# massmfg_tinyx4_v1_2.net
KiCad netlist of a schematic drawn in EAGLE
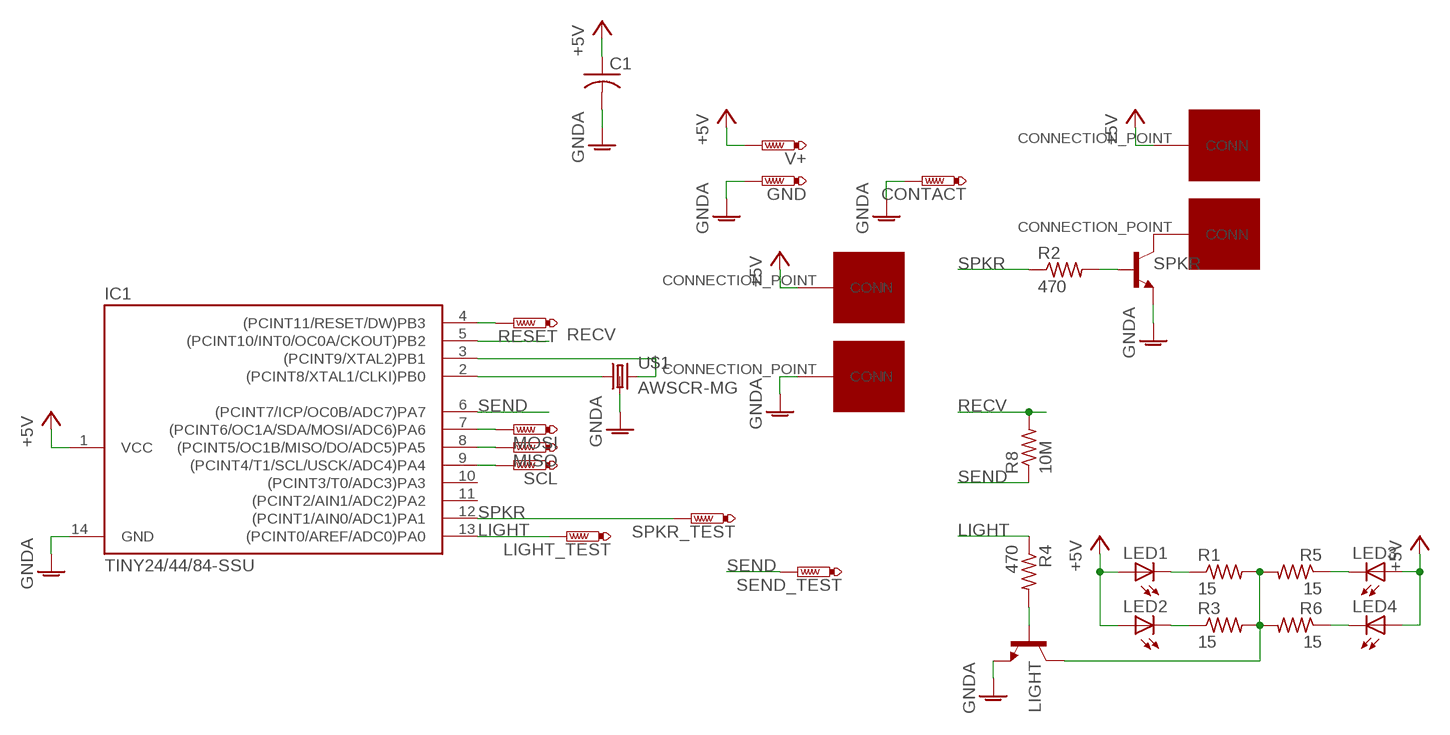
[diagram p0: schematic, sheet 1]

(export (version "E")
  (design (tool "Eeschema 10.0.6"))
  (components
    (comp (ref "C1")
      (value "C-USC0603")
      (footprint "eagle-import:C0603")
      (libsource (lib "eagle-import") (part "C-USC0603"))
    )
    (comp (ref "CONTACT")
      (value "PTR1")
      (footprint "eagle-import:P1-06")
      (libsource (lib "eagle-import") (part "PTR1"))
    )
    (comp (ref "GND")
      (value "PTR1")
      (footprint "eagle-import:P1-06")
      (libsource (lib "eagle-import") (part "PTR1"))
    )
    (comp (ref "IC1")
      (value "TINY24/44/84-SSU")
      (footprint "eagle-import:SOIC14")
      (libsource (lib "eagle-import") (part "TINY24/44/84-SSU"))
    )
    (comp (ref "LED1")
      (value "LEDOPTEK-DURIS5")
      (footprint "eagle-import:OPTEK-DURIS5")
      (libsource (lib "eagle-import") (part "LEDOPTEK-DURIS5"))
    )
    (comp (ref "LED2")
      (value "LEDOPTEK-DURIS5")
      (footprint "eagle-import:OPTEK-DURIS5")
      (libsource (lib "eagle-import") (part "LEDOPTEK-DURIS5"))
    )
    (comp (ref "LED3")
      (value "LEDOPTEK-DURIS5")
      (footprint "eagle-import:OPTEK-DURIS5")
      (libsource (lib "eagle-import") (part "LEDOPTEK-DURIS5"))
    )
    (comp (ref "LED4")
      (value "LEDOPTEK-DURIS5")
      (footprint "eagle-import:OPTEK-DURIS5")
      (libsource (lib "eagle-import") (part "LEDOPTEK-DURIS5"))
    )
    (comp (ref "LIGHT")
      (value "SOT23-BEC")
      (footprint "eagle-import:SOT23-BEC")
      (libsource (lib "eagle-import") (part "SOT23-BEC"))
    )
    (comp (ref "LIGHT_TEST")
      (value "PTR1")
      (footprint "eagle-import:P1-06")
      (libsource (lib "eagle-import") (part "PTR1"))
    )
    (comp (ref "MISO")
      (value "PTR1")
      (footprint "eagle-import:P1-06")
      (libsource (lib "eagle-import") (part "PTR1"))
    )
    (comp (ref "MOSI")
      (value "PTR1")
      (footprint "eagle-import:P1-06")
      (libsource (lib "eagle-import") (part "PTR1"))
    )
    (comp (ref "R1")
      (value "15")
      (footprint "eagle-import:M1206")
      (libsource (lib "eagle-import") (part "R-US_M1206"))
    )
    (comp (ref "R2")
      (value "470")
      (footprint "eagle-import:R0805")
      (libsource (lib "eagle-import") (part "R-US_R0805"))
    )
    (comp (ref "R3")
      (value "15")
      (footprint "eagle-import:M1206")
      (libsource (lib "eagle-import") (part "R-US_M1206"))
    )
    (comp (ref "R4")
      (value "470")
      (footprint "eagle-import:R0805")
      (libsource (lib "eagle-import") (part "R-US_R0805"))
    )
    (comp (ref "R5")
      (value "15")
      (footprint "eagle-import:M1206")
      (libsource (lib "eagle-import") (part "R-US_M1206"))
    )
    (comp (ref "R6")
      (value "15")
      (footprint "eagle-import:M1206")
      (libsource (lib "eagle-import") (part "R-US_M1206"))
    )
    (comp (ref "R8")
      (value "10M")
      (footprint "eagle-import:M1206")
      (libsource (lib "eagle-import") (part "R-US_M1206"))
    )
    (comp (ref "RESET")
      (value "PTR1")
      (footprint "eagle-import:P1-06")
      (libsource (lib "eagle-import") (part "PTR1"))
    )
    (comp (ref "SCL")
      (value "PTR1")
      (footprint "eagle-import:P1-06")
      (libsource (lib "eagle-import") (part "PTR1"))
    )
    (comp (ref "SEND_TEST")
      (value "PTR1")
      (footprint "eagle-import:P1-06")
      (libsource (lib "eagle-import") (part "PTR1"))
    )
    (comp (ref "SPEAKER_PLUS")
      (value "CONNECTION_POINT")
      (footprint "eagle-import:10X3_CONNECTION_POINT")
      (libsource (lib "eagle-import") (part "CONNECTION_POINT"))
    )
    (comp (ref "SPKR")
      (value "SOT23-BEC")
      (footprint "eagle-import:SOT23-BEC")
      (libsource (lib "eagle-import") (part "SOT23-BEC"))
    )
    (comp (ref "SPKR_MINUS")
      (value "CONNECTION_POINT")
      (footprint "eagle-import:10X3_CONNECTION_POINT")
      (libsource (lib "eagle-import") (part "CONNECTION_POINT"))
    )
    (comp (ref "SPKR_TEST")
      (value "PTR1")
      (footprint "eagle-import:P1-06")
      (libsource (lib "eagle-import") (part "PTR1"))
    )
    (comp (ref "U$1")
      (value "AWSCR-MG")
      (footprint "eagle-import:AWSCR-MG")
      (libsource (lib "eagle-import") (part "AWSCR-MG"))
    )
    (comp (ref "U$3")
      (value "CONNECTION_POINT")
      (footprint "eagle-import:10X3_CONNECTION_POINT")
      (libsource (lib "eagle-import") (part "CONNECTION_POINT"))
    )
    (comp (ref "U$5")
      (value "CONNECTION_POINT")
      (footprint "eagle-import:10X3_CONNECTION_POINT")
      (libsource (lib "eagle-import") (part "CONNECTION_POINT"))
    )
    (comp (ref "V+")
      (value "PTR1")
      (footprint "eagle-import:P1-06")
      (libsource (lib "eagle-import") (part "PTR1"))
    )
  )
  (nets
    (net (code "1") (name "+5V") (class "Default")
      (node (ref "C1") (pin "1") (pinfunction "1_1") (pintype "passive"))
      (node (ref "IC1") (pin "1") (pinfunction "VCC_1") (pintype "power_in"))
      (node (ref "LED1") (pin "ANODE") (pinfunction "A_ANODE") (pintype "passive"))
      (node (ref "LED2") (pin "ANODE") (pinfunction "A_ANODE") (pintype "passive"))
      (node (ref "LED3") (pin "ANODE") (pinfunction "A_ANODE") (pintype "passive"))
      (node (ref "LED4") (pin "ANODE") (pinfunction "A_ANODE") (pintype "passive"))
      (node (ref "SPEAKER_PLUS") (pin "CONNECTION_POINT") (pinfunction "CONN_CONNECTION_POINT") (pintype "bidirectional"))
      (node (ref "U$3") (pin "CONNECTION_POINT") (pinfunction "CONN_CONNECTION_POINT") (pintype "bidirectional"))
      (node (ref "V+") (pin "TP") (pinfunction "TP_TP") (pintype "input"))
    )
    (net (code "2") (name "/LIGHT") (class "Default")
      (node (ref "IC1") (pin "13") (pinfunction "(PCINT0/AREF/ADC0)PA0_13") (pintype "bidirectional"))
      (node (ref "LIGHT_TEST") (pin "TP") (pinfunction "TP_TP") (pintype "input"))
      (node (ref "R4") (pin "1") (pinfunction "1_1") (pintype "passive"))
    )
    (net (code "3") (name "/RECV") (class "Default")
      (node (ref "IC1") (pin "5") (pinfunction "(PCINT10/INT0/OC0A/CKOUT)PB2_5") (pintype "bidirectional"))
      (node (ref "R8") (pin "2") (pinfunction "2_2") (pintype "passive"))
    )
    (net (code "4") (name "/SEND") (class "Default")
      (node (ref "IC1") (pin "6") (pinfunction "(PCINT7/ICP/OC0B/ADC7)PA7_6") (pintype "bidirectional"))
      (node (ref "R8") (pin "1") (pinfunction "1_1") (pintype "passive"))
      (node (ref "SEND_TEST") (pin "TP") (pinfunction "TP_TP") (pintype "input"))
    )
    (net (code "5") (name "/SPKR") (class "Default")
      (node (ref "IC1") (pin "12") (pinfunction "(PCINT1/AIN0/ADC1)PA1_12") (pintype "bidirectional"))
      (node (ref "R2") (pin "1") (pinfunction "1_1") (pintype "passive"))
      (node (ref "SPKR_TEST") (pin "TP") (pinfunction "TP_TP") (pintype "input"))
    )
    (net (code "6") (name "GNDA") (class "Default")
      (node (ref "C1") (pin "2") (pinfunction "2_2") (pintype "passive"))
      (node (ref "CONTACT") (pin "TP") (pinfunction "TP_TP") (pintype "input"))
      (node (ref "GND") (pin "TP") (pinfunction "TP_TP") (pintype "input"))
      (node (ref "IC1") (pin "14") (pinfunction "GND_14") (pintype "power_in"))
      (node (ref "LIGHT") (pin "E") (pinfunction "E_E") (pintype "passive"))
      (node (ref "SPKR") (pin "E") (pinfunction "E_E") (pintype "passive"))
      (node (ref "U$1") (pin "GND") (pinfunction "3_GND") (pintype "passive"))
      (node (ref "U$5") (pin "CONNECTION_POINT") (pinfunction "CONN_CONNECTION_POINT") (pintype "bidirectional"))
    )
    (net (code "7") (name "Net-(IC1-(PCINT4{slash}T1{slash}SCL{slash}USCK{slash}ADC4)PA4)") (class "Default")
      (node (ref "IC1") (pin "9") (pinfunction "(PCINT4/T1/SCL/USCK/ADC4)PA4_9") (pintype "bidirectional"))
      (node (ref "SCL") (pin "TP") (pinfunction "TP_TP") (pintype "input"))
    )
    (net (code "8") (name "Net-(IC1-(PCINT5{slash}OC1B{slash}MISO{slash}DO{slash}ADC5)PA5)") (class "Default")
      (node (ref "IC1") (pin "8") (pinfunction "(PCINT5/OC1B/MISO/DO/ADC5)PA5_8") (pintype "bidirectional"))
      (node (ref "MISO") (pin "TP") (pinfunction "TP_TP") (pintype "input"))
    )
    (net (code "9") (name "Net-(IC1-(PCINT6{slash}OC1A{slash}SDA{slash}MOSI{slash}ADC6)PA6)") (class "Default")
      (node (ref "IC1") (pin "7") (pinfunction "(PCINT6/OC1A/SDA/MOSI/ADC6)PA6_7") (pintype "bidirectional"))
      (node (ref "MOSI") (pin "TP") (pinfunction "TP_TP") (pintype "input"))
    )
    (net (code "10") (name "Net-(IC1-(PCINT8{slash}XTAL1{slash}CLKI)PB0)") (class "Default")
      (node (ref "IC1") (pin "2") (pinfunction "(PCINT8/XTAL1/CLKI)PB0_2") (pintype "bidirectional"))
      (node (ref "U$1") (pin "IN") (pinfunction "1_IN") (pintype "passive"))
    )
    (net (code "11") (name "Net-(IC1-(PCINT9{slash}XTAL2)PB1)") (class "Default")
      (node (ref "IC1") (pin "3") (pinfunction "(PCINT9/XTAL2)PB1_3") (pintype "bidirectional"))
      (node (ref "U$1") (pin "OUT") (pinfunction "2_OUT") (pintype "passive"))
    )
    (net (code "12") (name "Net-(IC1-(PCINT11{slash}RESET{slash}DW)PB3)") (class "Default")
      (node (ref "IC1") (pin "4") (pinfunction "(PCINT11/RESET/DW)PB3_4") (pintype "bidirectional"))
      (node (ref "RESET") (pin "TP") (pinfunction "TP_TP") (pintype "input"))
    )
    (net (code "13") (name "Net-(LED1-C)") (class "Default")
      (node (ref "LED1") (pin "CATHODE") (pinfunction "C_CATHODE") (pintype "passive"))
      (node (ref "R1") (pin "1") (pinfunction "1_1") (pintype "passive"))
    )
    (net (code "14") (name "Net-(LED2-C)") (class "Default")
      (node (ref "LED2") (pin "CATHODE") (pinfunction "C_CATHODE") (pintype "passive"))
      (node (ref "R3") (pin "1") (pinfunction "1_1") (pintype "passive"))
    )
    (net (code "15") (name "Net-(LED3-C)") (class "Default")
      (node (ref "LED3") (pin "CATHODE") (pinfunction "C_CATHODE") (pintype "passive"))
      (node (ref "R5") (pin "1") (pinfunction "1_1") (pintype "passive"))
    )
    (net (code "16") (name "Net-(LED4-C)") (class "Default")
      (node (ref "LED4") (pin "CATHODE") (pinfunction "C_CATHODE") (pintype "passive"))
      (node (ref "R6") (pin "1") (pinfunction "1_1") (pintype "passive"))
    )
    (net (code "17") (name "Net-(LIGHT-PadB)") (class "Default")
      (node (ref "LIGHT") (pin "B") (pinfunction "B_B") (pintype "passive"))
      (node (ref "R4") (pin "2") (pinfunction "2_2") (pintype "passive"))
    )
    (net (code "18") (name "Net-(LIGHT-PadC)") (class "Default")
      (node (ref "LIGHT") (pin "C") (pinfunction "C_C") (pintype "passive"))
      (node (ref "R1") (pin "2") (pinfunction "2_2") (pintype "passive"))
      (node (ref "R3") (pin "2") (pinfunction "2_2") (pintype "passive"))
      (node (ref "R5") (pin "2") (pinfunction "2_2") (pintype "passive"))
      (node (ref "R6") (pin "2") (pinfunction "2_2") (pintype "passive"))
    )
    (net (code "19") (name "Net-(R2-Pad2)") (class "Default")
      (node (ref "R2") (pin "2") (pinfunction "2_2") (pintype "passive"))
      (node (ref "SPKR") (pin "B") (pinfunction "B_B") (pintype "passive"))
    )
    (net (code "20") (name "Net-(SPKR_MINUS-CONN)") (class "Default")
      (node (ref "SPKR") (pin "C") (pinfunction "C_C") (pintype "passive"))
      (node (ref "SPKR_MINUS") (pin "CONNECTION_POINT") (pinfunction "CONN_CONNECTION_POINT") (pintype "bidirectional"))
    )
    (net (code "21") (name "unconnected-(IC1-(PCINT2{slash}AIN1{slash}ADC2)PA2-Pad11)") (class "Default")
      (node (ref "IC1") (pin "11") (pinfunction "(PCINT2/AIN1/ADC2)PA2_11") (pintype "bidirectional"))
    )
    (net (code "22") (name "unconnected-(IC1-(PCINT3{slash}T0{slash}ADC3)PA3-Pad10)") (class "Default")
      (node (ref "IC1") (pin "10") (pinfunction "(PCINT3/T0/ADC3)PA3_10") (pintype "bidirectional"))
    )
  )
)
